# Sheet1.net
KiCad netlist of a schematic drawn in Altium Designer
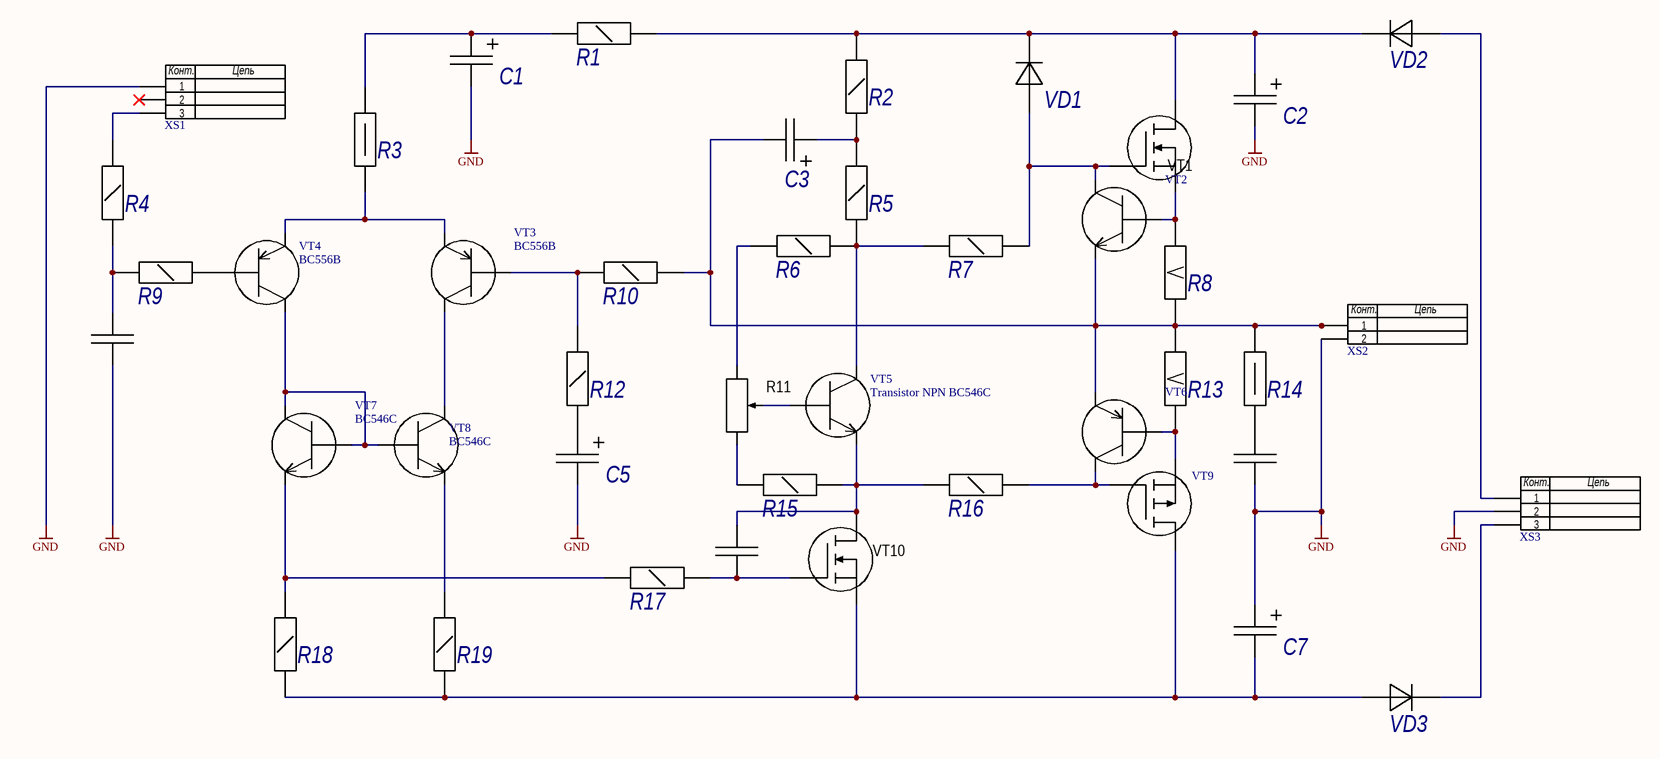
[diagram p0: Sheet1.SchDoc]

(export (version "E")
  (design (tool "Eeschema 10.0.6"))
  (components
    (comp (ref "C1")
      (value "2200uF 35V")
      (footprint "CAPPR350-800X700")
      (libsource (lib "Schlib1") (part "Cap Polarity 47uF 50V"))
    )
    (comp (ref "C2")
      (value "2200uF 35V")
      (footprint "CAPPR750-1600X3150")
      (libsource (lib "Schlib1") (part "Cap Polarity 2200uF 35V"))
    )
    (comp (ref "C3")
      (value "2200uF 35V")
      (footprint "CAPPR350-800X700")
      (libsource (lib "Schlib1") (part "Cap Polarity 47uF 50V"))
    )
    (comp (ref "C4")
      (value "Cap Ceramic 100pF")
      (footprint "CAPRR508-350X500X500")
      (libsource (lib "Schlib1") (part "Cap Ceramic 100pF"))
    )
    (comp (ref "C5")
      (value "100uF 100V")
      (footprint "CAPPR500-1000X2050")
      (libsource (lib "Schlib1") (part "Cap Polarity 100uF 100V"))
    )
    (comp (ref "C6")
      (value "Cap Ceramic 100pF")
      (footprint "CAPRR508-350X500X500")
      (libsource (lib "Schlib1") (part "Cap Ceramic 100pF"))
    )
    (comp (ref "C7")
      (value "2200uF 35V")
      (footprint "CAPPR750-1600X3150")
      (libsource (lib "Schlib1") (part "Cap Polarity 2200uF 35V"))
    )
    (comp (ref "https://www.eetimes.com/ic-audio-power-amplifiers-and-zobel-networks-one-size-does-not-fit-all/1")
      (value "2200uF 35V")
      (footprint "CAPR1000-400X1300X950")
      (libsource (lib "Schlib1") (part "Cap Film 0.68uF 250V"))
    )
    (comp (ref "R1")
      (value "Resistor 0.25W")
      (footprint "RES1016-630X250")
      (libsource (lib "Schlib1") (part "Resistor 0.25W"))
    )
    (comp (ref "R2")
      (value "Resistor 0.25W")
      (footprint "RES1016-630X250")
      (libsource (lib "Schlib1") (part "Resistor 0.25W"))
    )
    (comp (ref "R3")
      (value "Resistor 1W")
      (footprint "RES1651-1000X390")
      (libsource (lib "Schlib1") (part "Resistor 1W"))
    )
    (comp (ref "R4")
      (value "Resistor 0.25W")
      (footprint "RES1016-630X250")
      (libsource (lib "Schlib1") (part "Resistor 0.25W"))
    )
    (comp (ref "R5")
      (value "Resistor 0.25W")
      (footprint "RES1016-630X250")
      (libsource (lib "Schlib1") (part "Resistor 0.25W"))
    )
    (comp (ref "R6")
      (value "Resistor 0.25W")
      (footprint "RES1016-630X250")
      (libsource (lib "Schlib1") (part "Resistor 0.25W"))
    )
    (comp (ref "R7")
      (value "Resistor 0.25W")
      (footprint "RES1016-630X250")
      (libsource (lib "Schlib1") (part "Resistor 0.25W"))
    )
    (comp (ref "R8")
      (value "Resistor 5W")
      (footprint "RES_5W")
      (libsource (lib "Schlib1") (part "Resistor 5W"))
    )
    (comp (ref "R9")
      (value "Resistor 0.25W")
      (footprint "RES1016-630X250")
      (libsource (lib "Schlib1") (part "Resistor 0.25W"))
    )
    (comp (ref "R10")
      (value "Resistor 0.25W")
      (footprint "RES1016-630X250")
      (libsource (lib "Schlib1") (part "Resistor 0.25W"))
    )
    (comp (ref "R11")
      (value "~")
      (footprint "TRIM_BOURNS_3296W")
      (fields
        (field (name "MANUFACTURER") "Bourns")
        (field (name "PARTNUMBER") "3296W-1-103LF")
        (field (name "VALUEMANUFACTURERPARTNUMBER") "Resistor film, , , 3296W, 0.5W, -55...+125°C")
      )
      (libsource (lib "Schlib1") (part "Resistor Trimmer 1K"))
    )
    (comp (ref "R12")
      (value "Resistor 0.25W")
      (footprint "RES1016-630X250")
      (libsource (lib "Schlib1") (part "Resistor 0.25W"))
    )
    (comp (ref "R13")
      (value "Resistor 5W")
      (footprint "RES_5W")
      (libsource (lib "Schlib1") (part "Resistor 5W"))
    )
    (comp (ref "R14")
      (value "Resistor 1W")
      (footprint "RES1651-1000X390")
      (libsource (lib "Schlib1") (part "Resistor 1W"))
    )
    (comp (ref "R15")
      (value "Resistor 0.25W")
      (footprint "RES1016-630X250")
      (libsource (lib "Schlib1") (part "Resistor 0.25W"))
    )
    (comp (ref "R16")
      (value "Resistor 0.25W")
      (footprint "RES1016-630X250")
      (libsource (lib "Schlib1") (part "Resistor 0.25W"))
    )
    (comp (ref "R17")
      (value "Resistor 0.25W")
      (footprint "RES1016-630X250")
      (libsource (lib "Schlib1") (part "Resistor 0.25W"))
    )
    (comp (ref "R18")
      (value "Resistor 0.25W")
      (footprint "RES1016-630X250")
      (libsource (lib "Schlib1") (part "Resistor 0.25W"))
    )
    (comp (ref "R19")
      (value "Resistor 0.25W")
      (footprint "RES1016-630X250")
      (libsource (lib "Schlib1") (part "Resistor 0.25W"))
    )
    (comp (ref "VD1")
      (value "Diode 1N4002")
      (footprint "DO-41")
      (fields (field (name "PUBLISHER") "Andrew Danich"))
      (libsource (lib "Schlib1") (part "Diode 1N4002"))
    )
    (comp (ref "VD2")
      (value "Diode 15SQ045")
      (footprint "R6")
      (fields (field (name "PUBLISHER") "Andrew Danich"))
      (libsource (lib "Schlib1") (part "Diode 15SQ045"))
    )
    (comp (ref "VD3")
      (value "Diode 15SQ045")
      (footprint "R6")
      (fields (field (name "PUBLISHER") "Andrew Danich"))
      (libsource (lib "Schlib1") (part "Diode 15SQ045"))
    )
    (comp (ref "VT1") (value "~") (footprint "TO-220AB") (libsource (lib "Schlib1") (part "IRF510PBF")))
    (comp (ref "VT2") (value "BC546C") (footprint "TO-92-A") (libsource (lib "Schlib1") (part "BC546C")))
    (comp (ref "VT3") (value "BC556B") (footprint "TO-92-A") (libsource (lib "Schlib1") (part "BC556B")))
    (comp (ref "VT4") (value "BC556B") (footprint "TO-92-A") (libsource (lib "Schlib1") (part "BC556B")))
    (comp (ref "VT5")
      (value "Transistor NPN BC546C")
      (footprint "TO-92-A")
      (libsource (lib "Schlib1") (part "Transistor NPN BC546C"))
    )
    (comp (ref "VT6") (value "BC556B") (footprint "TO-92-A") (libsource (lib "Schlib1") (part "BC556B")))
    (comp (ref "VT7") (value "BC546C") (footprint "TO-92-A") (libsource (lib "Schlib1") (part "BC546C")))
    (comp (ref "VT8") (value "BC546C") (footprint "TO-92-A") (libsource (lib "Schlib1") (part "BC546C")))
    (comp (ref "VT9")
      (value "IRF9510PBF")
      (footprint "TO-220AB")
      (libsource (lib "Schlib1") (part "IRF9510PBF"))
    )
    (comp (ref "VT10")
      (value "~")
      (footprint "TO-92-A")
      (libsource (lib "Schlib1") (part "Transistor N-Mosfet BS170"))
    )
    (comp (ref "XS1")
      (value "Audio Connector 3 pin")
      (footprint "ST-025")
      (libsource (lib "Schlib1") (part "Audio Connector 3 pin"))
    )
    (comp (ref "XS2")
      (value "Connector Dynamic 2 pin")
      (footprint "15EDGRC-3.81-02P")
      (libsource (lib "Schlib1") (part "Connector Dynamic 2 pin"))
    )
    (comp (ref "XS3")
      (value "Connector Power 3 pin")
      (footprint "15EDGRC-3.81-03P")
      (libsource (lib "Schlib1") (part "Connector Power 3 pin"))
    )
  )
  (nets
    (net (code "1") (name "GND") (class "Default")
      (node (ref "C1") (pin "2") (pinfunction "2_2") (pintype "passive"))
      (node (ref "C2") (pin "2") (pinfunction "2_2") (pintype "passive"))
      (node (ref "C4") (pin "2") (pinfunction "2_2") (pintype "passive"))
      (node (ref "C5") (pin "2") (pinfunction "2_2") (pintype "passive"))
      (node (ref "C7") (pin "1") (pinfunction "1_1") (pintype "passive"))
      (node (ref "XS1") (pin "1") (pinfunction "1_1") (pintype "passive"))
      (node (ref "XS2") (pin "2") (pinfunction "2_2") (pintype "passive"))
      (node (ref "XS3") (pin "2") (pinfunction "2_2") (pintype "passive"))
      (node (ref "https://www.eetimes.com/ic-audio-power-amplifiers-and-zobel-networks-one-size-does-not-fit-all/1") (pin "2") (pinfunction "2_2") (pintype "passive"))
    )
    (net (code "2") (name "Net-(C1-Pad1)") (class "Default")
      (node (ref "C1") (pin "1") (pinfunction "1_1") (pintype "passive"))
      (node (ref "R1") (pin "1") (pinfunction "1_1") (pintype "passive"))
      (node (ref "R3") (pin "1") (pinfunction "1_1") (pintype "passive"))
    )
    (net (code "3") (name "Net-(C3-Pad1)") (class "Default")
      (node (ref "C3") (pin "1") (pinfunction "1_1") (pintype "passive"))
      (node (ref "R2") (pin "1") (pinfunction "1_1") (pintype "passive"))
      (node (ref "R5") (pin "2") (pinfunction "2_2") (pintype "passive"))
    )
    (net (code "4") (name "Net-(C4-Pad1)") (class "Default")
      (node (ref "C4") (pin "1") (pinfunction "1_1") (pintype "passive"))
      (node (ref "R4") (pin "1") (pinfunction "1_1") (pintype "passive"))
      (node (ref "R9") (pin "1") (pinfunction "1_1") (pintype "passive"))
    )
    (net (code "5") (name "Net-(C5-Pad1)") (class "Default")
      (node (ref "C5") (pin "1") (pinfunction "1_1") (pintype "passive"))
      (node (ref "R12") (pin "2") (pinfunction "2_2") (pintype "passive"))
    )
    (net (code "6") (name "Net-(R4-Pad2)") (class "Default")
      (node (ref "R4") (pin "2") (pinfunction "2_2") (pintype "passive"))
      (node (ref "XS1") (pin "3") (pinfunction "3_3") (pintype "passive"))
    )
    (net (code "7") (name "Net-(R11-Pad1)") (class "Default")
      (node (ref "R11") (pin "1") (pinfunction "1_1") (pintype "passive"))
      (node (ref "R6") (pin "1") (pinfunction "1_1") (pintype "passive"))
    )
    (net (code "8") (name "Net-(R11-Pad3)") (class "Default")
      (node (ref "R11") (pin "3") (pinfunction "3_3") (pintype "passive"))
      (node (ref "R15") (pin "2") (pinfunction "2_2") (pintype "passive"))
    )
    (net (code "9") (name "Net-(R14-Pad1)") (class "Default")
      (node (ref "R14") (pin "1") (pinfunction "1_1") (pintype "passive"))
      (node (ref "https://www.eetimes.com/ic-audio-power-amplifiers-and-zobel-networks-one-size-does-not-fit-all/1") (pin "1") (pinfunction "1_1") (pintype "passive"))
    )
    (net (code "10") (name "Net-(VD1-А)") (class "Default")
      (node (ref "R7") (pin "2") (pinfunction "2_2") (pintype "passive"))
      (node (ref "VD1") (pin "1") (pinfunction "А_1") (pintype "passive"))
      (node (ref "VT1") (pin "1") (pinfunction "G_1") (pintype "passive"))
      (node (ref "VT2") (pin "1") (pinfunction "К_1") (pintype "passive"))
    )
    (net (code "11") (name "Net-(VD1-К)") (class "Default")
      (node (ref "C2") (pin "1") (pinfunction "1_1") (pintype "passive"))
      (node (ref "R1") (pin "2") (pinfunction "2_2") (pintype "passive"))
      (node (ref "R2") (pin "2") (pinfunction "2_2") (pintype "passive"))
      (node (ref "VD1") (pin "2") (pinfunction "К_2") (pintype "passive"))
      (node (ref "VD2") (pin "2") (pinfunction "К_2") (pintype "passive"))
      (node (ref "VT1") (pin "2") (pinfunction "D_2") (pintype "passive"))
    )
    (net (code "12") (name "Net-(VD2-А)") (class "Default")
      (node (ref "VD2") (pin "1") (pinfunction "А_1") (pintype "passive"))
      (node (ref "XS3") (pin "1") (pinfunction "1_1") (pintype "passive"))
    )
    (net (code "13") (name "Net-(VD3-А)") (class "Default")
      (node (ref "C7") (pin "2") (pinfunction "2_2") (pintype "passive"))
      (node (ref "R18") (pin "1") (pinfunction "1_1") (pintype "passive"))
      (node (ref "R19") (pin "1") (pinfunction "1_1") (pintype "passive"))
      (node (ref "VD3") (pin "1") (pinfunction "А_1") (pintype "passive"))
      (node (ref "VT10") (pin "3") (pinfunction "S_3") (pintype "passive"))
      (node (ref "VT9") (pin "2") (pinfunction "D_2") (pintype "passive"))
    )
    (net (code "14") (name "Net-(VD3-К)") (class "Default")
      (node (ref "VD3") (pin "2") (pinfunction "К_2") (pintype "passive"))
      (node (ref "XS3") (pin "3") (pinfunction "3_3") (pintype "passive"))
    )
    (net (code "15") (name "Net-(VT1-S)") (class "Default")
      (node (ref "R8") (pin "2") (pinfunction "2_2") (pintype "passive"))
      (node (ref "VT1") (pin "3") (pinfunction "S_3") (pintype "passive"))
      (node (ref "VT2") (pin "2") (pinfunction "Б_2") (pintype "passive"))
    )
    (net (code "16") (name "Net-(VT2-Э)") (class "Default")
      (node (ref "C3") (pin "2") (pinfunction "2_2") (pintype "passive"))
      (node (ref "R10") (pin "2") (pinfunction "2_2") (pintype "passive"))
      (node (ref "R13") (pin "2") (pinfunction "2_2") (pintype "passive"))
      (node (ref "R14") (pin "2") (pinfunction "2_2") (pintype "passive"))
      (node (ref "R8") (pin "1") (pinfunction "1_1") (pintype "passive"))
      (node (ref "VT2") (pin "3") (pinfunction "Э_3") (pintype "passive"))
      (node (ref "VT6") (pin "3") (pinfunction "Э_3") (pintype "passive"))
      (node (ref "XS2") (pin "1") (pinfunction "1_1") (pintype "passive"))
    )
    (net (code "17") (name "Net-(VT3-Б)") (class "Default")
      (node (ref "R10") (pin "1") (pinfunction "1_1") (pintype "passive"))
      (node (ref "R12") (pin "1") (pinfunction "1_1") (pintype "passive"))
      (node (ref "VT3") (pin "2") (pinfunction "Б_2") (pintype "passive"))
    )
    (net (code "18") (name "Net-(VT3-К)") (class "Default")
      (node (ref "VT3") (pin "1") (pinfunction "К_1") (pintype "passive"))
      (node (ref "VT8") (pin "1") (pinfunction "К_1") (pintype "passive"))
    )
    (net (code "19") (name "Net-(VT3-Э)") (class "Default")
      (node (ref "R3") (pin "2") (pinfunction "2_2") (pintype "passive"))
      (node (ref "VT3") (pin "3") (pinfunction "Э_3") (pintype "passive"))
      (node (ref "VT4") (pin "3") (pinfunction "Э_3") (pintype "passive"))
    )
    (net (code "20") (name "Net-(VT4-Б)") (class "Default")
      (node (ref "R9") (pin "2") (pinfunction "2_2") (pintype "passive"))
      (node (ref "VT4") (pin "2") (pinfunction "Б_2") (pintype "passive"))
    )
    (net (code "21") (name "Net-(VT4-К)") (class "Default")
      (node (ref "VT4") (pin "1") (pinfunction "К_1") (pintype "passive"))
      (node (ref "VT7") (pin "1") (pinfunction "К_1") (pintype "passive"))
      (node (ref "VT7") (pin "2") (pinfunction "Б_2") (pintype "passive"))
      (node (ref "VT8") (pin "2") (pinfunction "Б_2") (pintype "passive"))
    )
    (net (code "22") (name "Net-(VT5-Б)") (class "Default")
      (node (ref "R11") (pin "2") (pinfunction "2_2") (pintype "passive"))
      (node (ref "VT5") (pin "2") (pinfunction "Б_2") (pintype "passive"))
    )
    (net (code "23") (name "Net-(VT5-К)") (class "Default")
      (node (ref "R5") (pin "1") (pinfunction "1_1") (pintype "passive"))
      (node (ref "R6") (pin "2") (pinfunction "2_2") (pintype "passive"))
      (node (ref "R7") (pin "1") (pinfunction "1_1") (pintype "passive"))
      (node (ref "VT5") (pin "1") (pinfunction "К_1") (pintype "passive"))
    )
    (net (code "24") (name "Net-(VT6-Б)") (class "Default")
      (node (ref "R13") (pin "1") (pinfunction "1_1") (pintype "passive"))
      (node (ref "VT6") (pin "2") (pinfunction "Б_2") (pintype "passive"))
      (node (ref "VT9") (pin "3") (pinfunction "S_3") (pintype "passive"))
    )
    (net (code "25") (name "Net-(VT6-К)") (class "Default")
      (node (ref "R16") (pin "2") (pinfunction "2_2") (pintype "passive"))
      (node (ref "VT6") (pin "1") (pinfunction "К_1") (pintype "passive"))
      (node (ref "VT9") (pin "1") (pinfunction "G_1") (pintype "passive"))
    )
    (net (code "26") (name "Net-(VT7-Э)") (class "Default")
      (node (ref "R17") (pin "2") (pinfunction "2_2") (pintype "passive"))
      (node (ref "R18") (pin "2") (pinfunction "2_2") (pintype "passive"))
      (node (ref "VT7") (pin "3") (pinfunction "Э_3") (pintype "passive"))
    )
    (net (code "27") (name "Net-(VT8-Э)") (class "Default")
      (node (ref "R19") (pin "2") (pinfunction "2_2") (pintype "passive"))
      (node (ref "VT8") (pin "3") (pinfunction "Э_3") (pintype "passive"))
    )
    (net (code "28") (name "Net-(VT10-D)") (class "Default")
      (node (ref "C6") (pin "2") (pinfunction "2_2") (pintype "passive"))
      (node (ref "R15") (pin "1") (pinfunction "1_1") (pintype "passive"))
      (node (ref "R16") (pin "1") (pinfunction "1_1") (pintype "passive"))
      (node (ref "VT10") (pin "1") (pinfunction "D_1") (pintype "passive"))
      (node (ref "VT5") (pin "3") (pinfunction "Э_3") (pintype "passive"))
    )
    (net (code "29") (name "Net-(VT10-G)") (class "Default")
      (node (ref "C6") (pin "1") (pinfunction "1_1") (pintype "passive"))
      (node (ref "R17") (pin "1") (pinfunction "1_1") (pintype "passive"))
      (node (ref "VT10") (pin "2") (pinfunction "G_2") (pintype "passive"))
    )
    (net (code "30") (name "unconnected-(XS1-Pad2)") (class "Default")
      (node (ref "XS1") (pin "2") (pinfunction "2_2") (pintype "passive+no_connect"))
    )
  )
)
